# attiny85_arduino_as_ISP_programmer.net
KiCad netlist of a schematic drawn in EAGLE
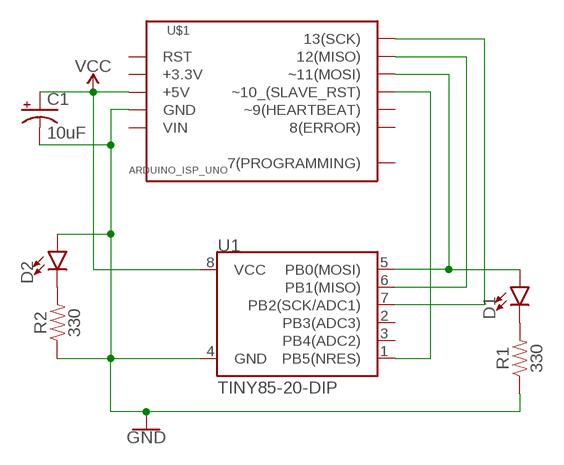
[diagram p0: schematic, sheet 1]

(export (version "E")
  (design (tool "Eeschema 10.0.6"))
  (components
    (comp (ref "C1")
      (value "10uF")
      (footprint "eagle-import:CPOL-RADIAL-2.5MM-5MM")
      (libsource (lib "eagle-import") (part "10UF-POLAR-RADIAL-2.5MM-25V-20%"))
    )
    (comp (ref "D1")
      (value "LED3MM")
      (footprint "eagle-import:LED_3MM")
      (libsource (lib "eagle-import") (part "LED3MM"))
    )
    (comp (ref "D2")
      (value "LED3MM")
      (footprint "eagle-import:LED_3MM")
      (libsource (lib "eagle-import") (part "LED3MM"))
    )
    (comp (ref "R1")
      (value "330")
      (footprint "eagle-import:AXIAL-0.3")
      (libsource (lib "eagle-import") (part "330OHM-HORIZ-1/10W-5%"))
    )
    (comp (ref "R2")
      (value "330")
      (footprint "eagle-import:AXIAL-0.3")
      (libsource (lib "eagle-import") (part "330OHM-HORIZ-1/10W-5%"))
    )
    (comp (ref "U$1")
      (value "ARDUINO_ISP_UNO")
      (footprint "eagle-import:ARDUINO_UNO_ISP")
      (libsource (lib "eagle-import") (part "ARDUINO_ISP_UNO"))
    )
    (comp (ref "U1")
      (value "TINY85-20-DIP")
      (footprint "eagle-import:DIP08_MCU")
      (libsource (lib "eagle-import") (part "ATTINY45TINY85-20-DIP"))
    )
  )
  (nets
    (net (code "1") (name "GND") (class "Default")
      (node (ref "C1") (pin "2") (pinfunction "-_2") (pintype "passive"))
      (node (ref "D2") (pin "A") (pinfunction "A_A") (pintype "passive"))
      (node (ref "R1") (pin "P$1") (pinfunction "1_P$1") (pintype "passive"))
      (node (ref "R2") (pin "P$1") (pinfunction "1_P$1") (pintype "passive"))
      (node (ref "U$1") (pin "GND@1") (pinfunction "GND_GND@1") (pintype "bidirectional"))
      (node (ref "U$1") (pin "GND@2") (pinfunction "GND_GND@2") (pintype "bidirectional"))
      (node (ref "U1") (pin "4") (pinfunction "GND_4") (pintype "bidirectional"))
    )
    (net (code "2") (name "Net-(D1-C)") (class "Default")
      (node (ref "D1") (pin "K") (pinfunction "C_K") (pintype "passive"))
      (node (ref "R1") (pin "P$2") (pinfunction "2_P$2") (pintype "passive"))
    )
    (net (code "3") (name "Net-(D2-C)") (class "Default")
      (node (ref "D2") (pin "K") (pinfunction "C_K") (pintype "passive"))
      (node (ref "R2") (pin "P$2") (pinfunction "2_P$2") (pintype "passive"))
    )
    (net (code "4") (name "Net-(U$1-12(MISO))") (class "Default")
      (node (ref "U$1") (pin "D12") (pinfunction "12(MISO)_D12") (pintype "bidirectional"))
      (node (ref "U1") (pin "6") (pinfunction "PB1(MISO)_6") (pintype "bidirectional"))
    )
    (net (code "5") (name "Net-(U$1-13(SCK))") (class "Default")
      (node (ref "U$1") (pin "D13") (pinfunction "13(SCK)_D13") (pintype "bidirectional"))
      (node (ref "U1") (pin "7") (pinfunction "PB2(SCK/ADC1)_7") (pintype "bidirectional"))
    )
    (net (code "6") (name "Net-(U$1-~{10_(SLAVE_RST}))") (class "Default")
      (node (ref "U$1") (pin "D10") (pinfunction "~{10_(SLAVE_RST})_D10") (pintype "bidirectional"))
      (node (ref "U1") (pin "1") (pinfunction "PB5(NRES)_1") (pintype "bidirectional"))
    )
    (net (code "7") (name "Net-(U$1-~{11(MOSI}))") (class "Default")
      (node (ref "D1") (pin "A") (pinfunction "A_A") (pintype "passive"))
      (node (ref "U$1") (pin "D11") (pinfunction "~{11(MOSI})_D11") (pintype "bidirectional"))
      (node (ref "U1") (pin "5") (pinfunction "PB0(MOSI)_5") (pintype "bidirectional"))
    )
    (net (code "8") (name "VCC") (class "Default")
      (node (ref "C1") (pin "1") (pinfunction "+_1") (pintype "passive"))
      (node (ref "U$1") (pin "5V") (pinfunction "+5V_5V") (pintype "bidirectional"))
      (node (ref "U1") (pin "8") (pinfunction "VCC_8") (pintype "bidirectional"))
    )
    (net (code "9") (name "unconnected-(U$1-+3.3V-Pad3.3V)") (class "Default")
      (node (ref "U$1") (pin "3.3V") (pinfunction "+3.3V_3.3V") (pintype "bidirectional"))
    )
    (net (code "10") (name "unconnected-(U$1-7(PROGRAMMING)-PadD7)") (class "Default")
      (node (ref "U$1") (pin "D7") (pinfunction "7(PROGRAMMING)_D7") (pintype "bidirectional"))
    )
    (net (code "11") (name "unconnected-(U$1-8(ERROR)-PadD8)") (class "Default")
      (node (ref "U$1") (pin "D8") (pinfunction "8(ERROR)_D8") (pintype "bidirectional"))
    )
    (net (code "12") (name "unconnected-(U$1-PadRST)") (class "Default")
      (node (ref "U$1") (pin "RST") (pinfunction "RST_RST") (pintype "bidirectional"))
    )
    (net (code "13") (name "unconnected-(U$1-PadVIN)") (class "Default")
      (node (ref "U$1") (pin "VIN") (pinfunction "VIN_VIN") (pintype "bidirectional"))
    )
    (net (code "14") (name "unconnected-(U$1-~{9(HEARTBEAT})-PadD9)") (class "Default")
      (node (ref "U$1") (pin "D9") (pinfunction "~{9(HEARTBEAT})_D9") (pintype "bidirectional"))
    )
    (net (code "15") (name "unconnected-(U1-PB3(ADC3)-Pad2)") (class "Default")
      (node (ref "U1") (pin "2") (pinfunction "PB3(ADC3)_2") (pintype "bidirectional"))
    )
    (net (code "16") (name "unconnected-(U1-PB4(ADC2)-Pad3)") (class "Default")
      (node (ref "U1") (pin "3") (pinfunction "PB4(ADC2)_3") (pintype "bidirectional"))
    )
  )
)
